# CAN.net
KiCad netlist of a schematic drawn in Altium Designer
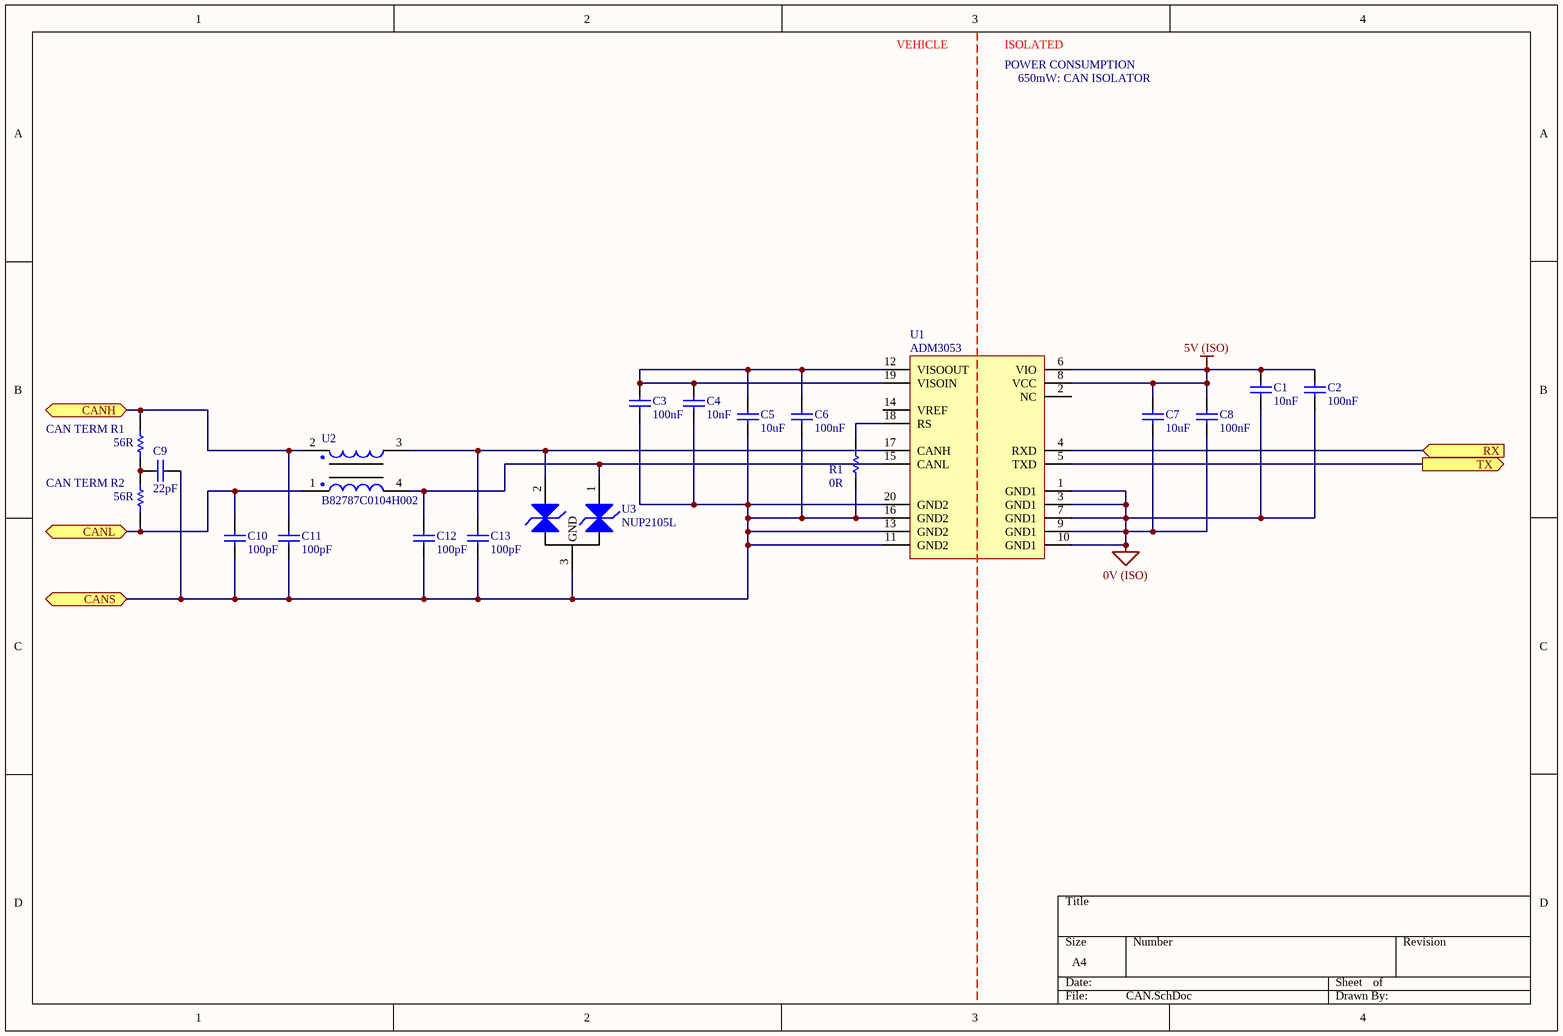
[diagram p0: CAN.SchDoc]

(export (version "E")
  (design (tool "Eeschema 10.0.6"))
  (components
    (comp (ref "C1")
      (value "10nF")
      (footprint "1206")
      (fields
        (field (name "PART NUMBER") "GCM3195C2A103JA16D")
        (field (name "TOLERANCE") "5%")
        (field (name "MANUFACTURER") "muRata")
      )
      (libsource (lib "ts_20-standard-library") (part "Capacitor"))
    )
    (comp (ref "C2")
      (value "100nF")
      (footprint "0805")
      (fields
        (field (name "PART NUMBER") "GCM21BR71E104KA37L")
        (field (name "TOLERANCE") "10%")
        (field (name "MANUFACTURER") "muRata")
      )
      (libsource (lib "ts_20-standard-library") (part "Capacitor"))
    )
    (comp (ref "C3")
      (value "100nF")
      (footprint "0805")
      (fields
        (field (name "PART NUMBER") "GCM21BR71E104KA37L")
        (field (name "TOLERANCE") "10%")
        (field (name "MANUFACTURER") "muRata")
      )
      (libsource (lib "ts_20-standard-library") (part "Capacitor"))
    )
    (comp (ref "C4")
      (value "10nF")
      (footprint "1206")
      (fields
        (field (name "PART NUMBER") "GCM3195C2A103JA16D")
        (field (name "TOLERANCE") "5%")
        (field (name "MANUFACTURER") "muRata")
      )
      (libsource (lib "ts_20-standard-library") (part "Capacitor"))
    )
    (comp (ref "C5")
      (value "10uF")
      (footprint "0805")
      (fields
        (field (name "PART NUMBER") "GRM21BR6YA106KE43L")
        (field (name "TOLERANCE") "10%")
        (field (name "MANUFACTURER") "muRata")
      )
      (libsource (lib "ts_20-standard-library") (part "Capacitor"))
    )
    (comp (ref "C6")
      (value "100nF")
      (footprint "0805")
      (fields
        (field (name "PART NUMBER") "GCM21BR71E104KA37L")
        (field (name "TOLERANCE") "10%")
        (field (name "MANUFACTURER") "muRata")
      )
      (libsource (lib "ts_20-standard-library") (part "Capacitor"))
    )
    (comp (ref "C7")
      (value "10uF")
      (footprint "0805")
      (fields
        (field (name "PART NUMBER") "GRM21BR6YA106KE43L")
        (field (name "TOLERANCE") "10%")
        (field (name "MANUFACTURER") "muRata")
      )
      (libsource (lib "ts_20-standard-library") (part "Capacitor"))
    )
    (comp (ref "C8")
      (value "100nF")
      (footprint "0805")
      (fields
        (field (name "PART NUMBER") "GCM21BR71E104KA37L")
        (field (name "TOLERANCE") "10%")
        (field (name "MANUFACTURER") "muRata")
      )
      (libsource (lib "ts_20-standard-library") (part "Capacitor"))
    )
    (comp (ref "C9")
      (value "22pF")
      (footprint "0805")
      (fields
        (field (name "PART NUMBER") "GCM21B5C1H220JA37L")
        (field (name "TOLERANCE") "5%")
        (field (name "MANUFACTURER") "muRata")
      )
      (libsource (lib "ts_20-standard-library") (part "Capacitor"))
    )
    (comp (ref "C10")
      (value "100pF")
      (footprint "0805")
      (fields
        (field (name "PART NUMBER") "GCM21B5C1H101JA37L")
        (field (name "TOLERANCE") "5%")
        (field (name "MANUFACTURER") "muRata")
      )
      (libsource (lib "ts_20-standard-library") (part "Capacitor"))
    )
    (comp (ref "C11")
      (value "100pF")
      (footprint "0805")
      (fields
        (field (name "PART NUMBER") "GCM21B5C1H101JA37L")
        (field (name "TOLERANCE") "5%")
        (field (name "MANUFACTURER") "muRata")
      )
      (libsource (lib "ts_20-standard-library") (part "Capacitor"))
    )
    (comp (ref "C12")
      (value "100pF")
      (footprint "0805")
      (fields
        (field (name "PART NUMBER") "GCM21B5C1H101JA37L")
        (field (name "TOLERANCE") "5%")
        (field (name "MANUFACTURER") "muRata")
      )
      (libsource (lib "ts_20-standard-library") (part "Capacitor"))
    )
    (comp (ref "C13")
      (value "100pF")
      (footprint "0805")
      (fields
        (field (name "PART NUMBER") "GCM21B5C1H101JA37L")
        (field (name "TOLERANCE") "5%")
        (field (name "MANUFACTURER") "muRata")
      )
      (libsource (lib "ts_20-standard-library") (part "Capacitor"))
    )
    (comp (ref "CAN TERM R1")
      (value "56R")
      (footprint "0805")
      (fields
        (field (name "PART NUMBER") "RC0805FR0756RL")
        (field (name "MANUFACTURER") "YAGEO")
        (field (name "TOLERANCE") "0.01")
      )
      (libsource (lib "ts_20-standard-library") (part "Resistor"))
    )
    (comp (ref "CAN TERM R2")
      (value "56R")
      (footprint "0805")
      (fields
        (field (name "PART NUMBER") "RC0805FR0756RL")
        (field (name "MANUFACTURER") "YAGEO")
        (field (name "TOLERANCE") "0.01")
      )
      (libsource (lib "ts_20-standard-library") (part "Resistor"))
    )
    (comp (ref "R1")
      (value "0R")
      (footprint "0805")
      (fields
        (field (name "TOLERANCE") "0.01")
        (field (name "PART NUMBER") "RC0805FR070RL")
        (field (name "MANUFACTURER") "YAGEO")
      )
      (libsource (lib "ts_19-standard-library") (part "Resistor"))
    )
    (comp (ref "U1")
      (value "ADM3053")
      (footprint "AD SOIC-W 20")
      (description "Isolated CAN Transceiver")
      (fields
        (field (name "MANUFACTURER") "Analogue Devices")
        (field (name "DIGIKEY PART NUMBER") "ADM3053BRWZ-ND")
      )
      (libsource (lib "ts_20-standard-library") (part "ADM3053"))
    )
    (comp (ref "U2")
      (value "B82787C0104H002")
      (footprint "TDK 4-PC Pad")
      (description "Common mode choke intended for CANBUS 150mA 50V)")
      (fields
        (field (name "MANUFACTURER") "EPCOS (TDK)")
        (field (name "DIGIKEY PART NUMBER") "495-4598-2-ND")
      )
      (libsource (lib "ts_20-standard-library") (part "B82787C0104H002"))
    )
    (comp (ref "U3")
      (value "NUP2105L")
      (footprint "ON SOT-23")
      (description "Dual Line CAN Bus Protector")
      (fields
        (field (name "MANUFACTURER") "ON Semiconductor")
        (field (name "DIGIKEY PART NUMBER") "NUP2105LT1GOSCT-ND")
      )
      (libsource (lib "ts_20-standard-library") (part "NUP2105L"))
    )
  )
  (nets
    (net (code "1") (name "/CANH") (class "Default")
      (node (ref "C11") (pin "2") (pinfunction "2_2") (pintype "passive"))
      (node (ref "CAN TERM R1") (pin "2") (pinfunction "2_2") (pintype "passive"))
      (node (ref "U2") (pin "2") (pinfunction "2_2") (pintype "passive"))
    )
    (net (code "2") (name "/CANL") (class "Default")
      (node (ref "C10") (pin "2") (pinfunction "2_2") (pintype "passive"))
      (node (ref "CAN TERM R2") (pin "1") (pinfunction "1_1") (pintype "passive"))
      (node (ref "U2") (pin "1") (pinfunction "1_1") (pintype "passive"))
    )
    (net (code "3") (name "/CANS") (class "Default")
      (node (ref "C10") (pin "1") (pinfunction "1_1") (pintype "passive"))
      (node (ref "C11") (pin "1") (pinfunction "1_1") (pintype "passive"))
      (node (ref "C12") (pin "1") (pinfunction "1_1") (pintype "passive"))
      (node (ref "C13") (pin "1") (pinfunction "1_1") (pintype "passive"))
      (node (ref "C3") (pin "1") (pinfunction "1_1") (pintype "passive"))
      (node (ref "C4") (pin "1") (pinfunction "1_1") (pintype "passive"))
      (node (ref "C5") (pin "1") (pinfunction "1_1") (pintype "passive"))
      (node (ref "C6") (pin "1") (pinfunction "1_1") (pintype "passive"))
      (node (ref "C9") (pin "1") (pinfunction "1_1") (pintype "passive"))
      (node (ref "R1") (pin "1") (pinfunction "1_1") (pintype "passive"))
      (node (ref "U1") (pin "11") (pinfunction "GND2_11") (pintype "passive"))
      (node (ref "U1") (pin "13") (pinfunction "GND2_13") (pintype "passive"))
      (node (ref "U1") (pin "16") (pinfunction "GND2_16") (pintype "passive"))
      (node (ref "U1") (pin "20") (pinfunction "GND2_20") (pintype "passive"))
      (node (ref "U3") (pin "3") (pinfunction "GND_3") (pintype "power_in"))
    )
    (net (code "4") (name "/RX") (class "Default")
      (node (ref "U1") (pin "4") (pinfunction "RXD_4") (pintype "passive"))
    )
    (net (code "5") (name "/TX") (class "Default")
      (node (ref "U1") (pin "5") (pinfunction "TXD_5") (pintype "passive"))
    )
    (net (code "6") (name "0V (ISO)") (class "Default")
      (node (ref "C1") (pin "1") (pinfunction "1_1") (pintype "passive"))
      (node (ref "C2") (pin "1") (pinfunction "1_1") (pintype "passive"))
      (node (ref "C7") (pin "1") (pinfunction "1_1") (pintype "passive"))
      (node (ref "C8") (pin "1") (pinfunction "1_1") (pintype "passive"))
      (node (ref "U1") (pin "1") (pinfunction "GND1_1") (pintype "passive"))
      (node (ref "U1") (pin "10") (pinfunction "GND1_10") (pintype "passive"))
      (node (ref "U1") (pin "3") (pinfunction "GND1_3") (pintype "passive"))
      (node (ref "U1") (pin "7") (pinfunction "GND1_7") (pintype "passive"))
      (node (ref "U1") (pin "9") (pinfunction "GND1_9") (pintype "passive"))
    )
    (net (code "7") (name "5V (ISO)") (class "Default")
      (node (ref "C1") (pin "2") (pinfunction "2_2") (pintype "passive"))
      (node (ref "C2") (pin "2") (pinfunction "2_2") (pintype "passive"))
      (node (ref "C7") (pin "2") (pinfunction "2_2") (pintype "passive"))
      (node (ref "C8") (pin "2") (pinfunction "2_2") (pintype "passive"))
      (node (ref "U1") (pin "6") (pinfunction "VIO_6") (pintype "passive"))
      (node (ref "U1") (pin "8") (pinfunction "VCC_8") (pintype "passive"))
    )
    (net (code "8") (name "Net-(C9-Pad2)") (class "Default")
      (node (ref "C9") (pin "2") (pinfunction "2_2") (pintype "passive"))
      (node (ref "CAN TERM R1") (pin "1") (pinfunction "1_1") (pintype "passive"))
      (node (ref "CAN TERM R2") (pin "2") (pinfunction "2_2") (pintype "passive"))
    )
    (net (code "9") (name "Net-(U1-CANH)") (class "Default")
      (node (ref "C13") (pin "2") (pinfunction "2_2") (pintype "passive"))
      (node (ref "U1") (pin "17") (pinfunction "CANH_17") (pintype "passive"))
      (node (ref "U2") (pin "3") (pinfunction "3_3") (pintype "power_in"))
      (node (ref "U3") (pin "2") (pinfunction "CAN_L_2") (pintype "passive"))
    )
    (net (code "10") (name "Net-(U1-CANL)") (class "Default")
      (node (ref "C12") (pin "2") (pinfunction "2_2") (pintype "passive"))
      (node (ref "U1") (pin "15") (pinfunction "CANL_15") (pintype "passive"))
      (node (ref "U2") (pin "4") (pinfunction "4_4") (pintype "passive"))
      (node (ref "U3") (pin "1") (pinfunction "CAN_H_1") (pintype "passive"))
    )
    (net (code "11") (name "Net-(U1-RS)") (class "Default")
      (node (ref "R1") (pin "2") (pinfunction "2_2") (pintype "passive"))
      (node (ref "U1") (pin "18") (pinfunction "RS_18") (pintype "passive"))
    )
    (net (code "12") (name "Net-(U1-VISOIN)") (class "Default")
      (node (ref "C3") (pin "2") (pinfunction "2_2") (pintype "passive"))
      (node (ref "C4") (pin "2") (pinfunction "2_2") (pintype "passive"))
      (node (ref "C5") (pin "2") (pinfunction "2_2") (pintype "passive"))
      (node (ref "C6") (pin "2") (pinfunction "2_2") (pintype "passive"))
      (node (ref "U1") (pin "12") (pinfunction "VISOOUT_12") (pintype "passive"))
      (node (ref "U1") (pin "19") (pinfunction "VISOIN_19") (pintype "passive"))
    )
    (net (code "13") (name "unconnected-(U1-NC-Pad2)") (class "Default")
      (node (ref "U1") (pin "2") (pinfunction "NC_2") (pintype "passive"))
    )
    (net (code "14") (name "unconnected-(U1-VREF-Pad14)") (class "Default")
      (node (ref "U1") (pin "14") (pinfunction "VREF_14") (pintype "passive"))
    )
  )
)
